# VF_Sine_CPU_Mainboard.net
KiCad netlist of a schematic drawn in EAGLE
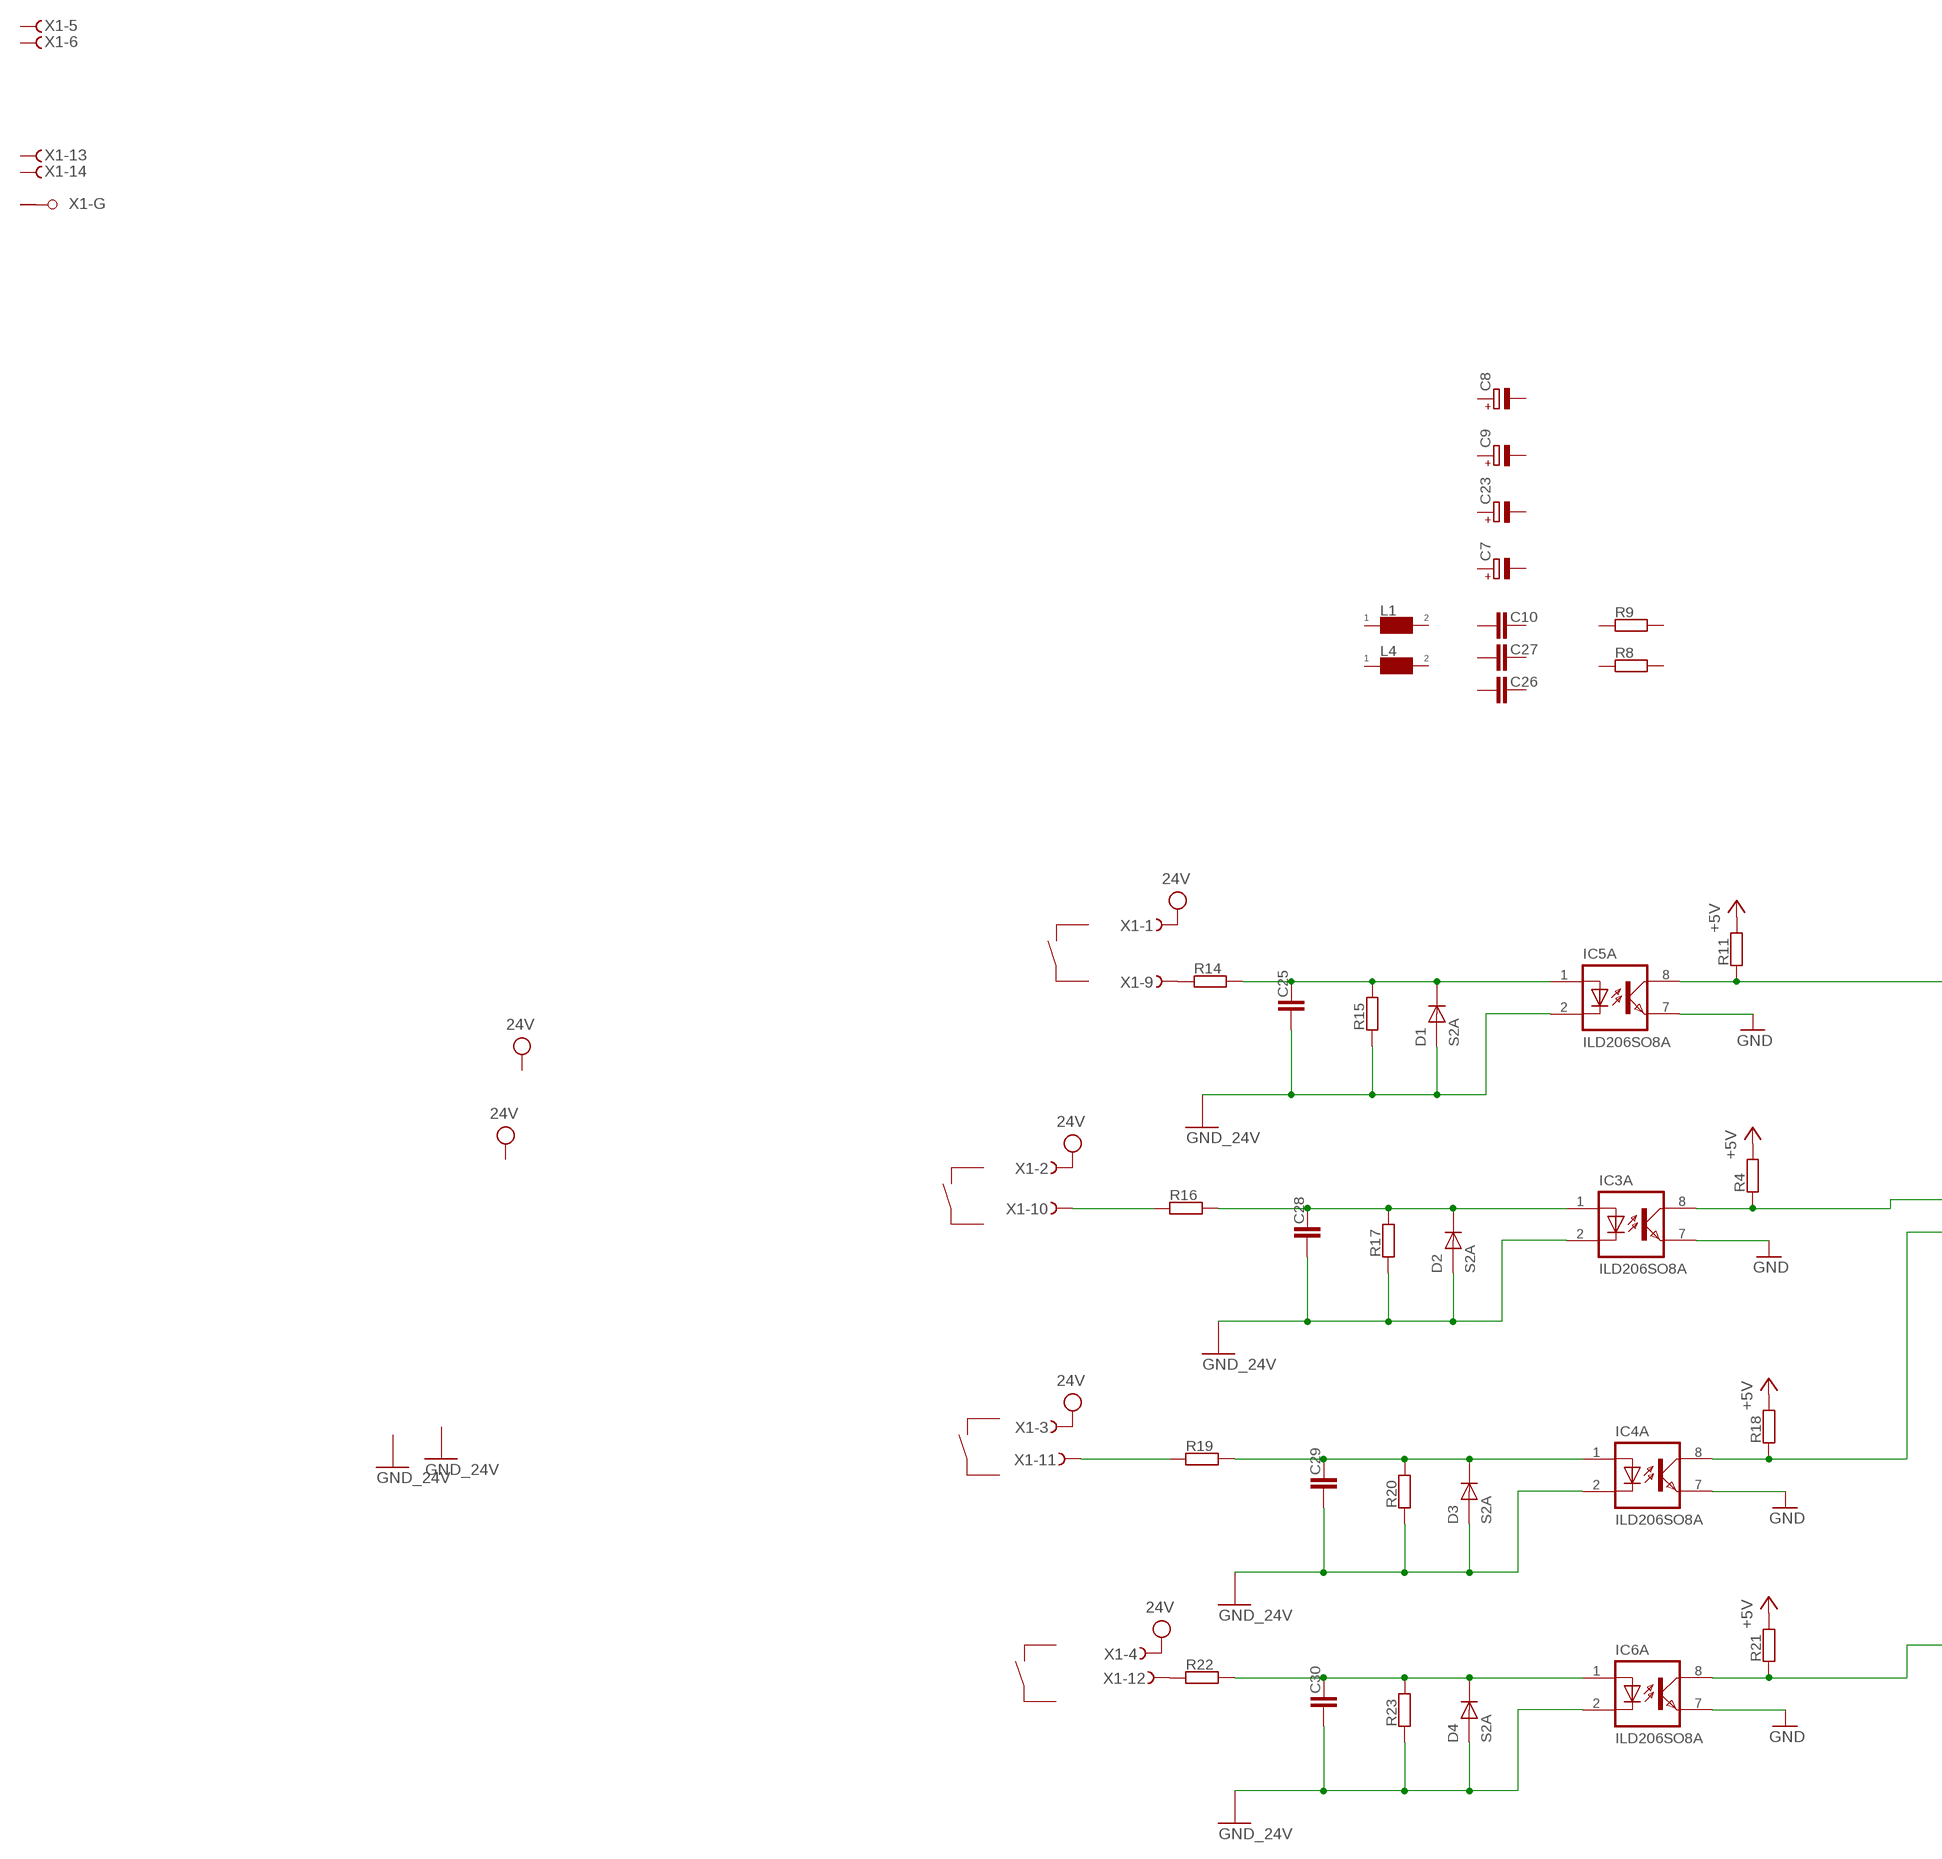
[diagram p0: schematic, sheet 1, part 1 of 3]
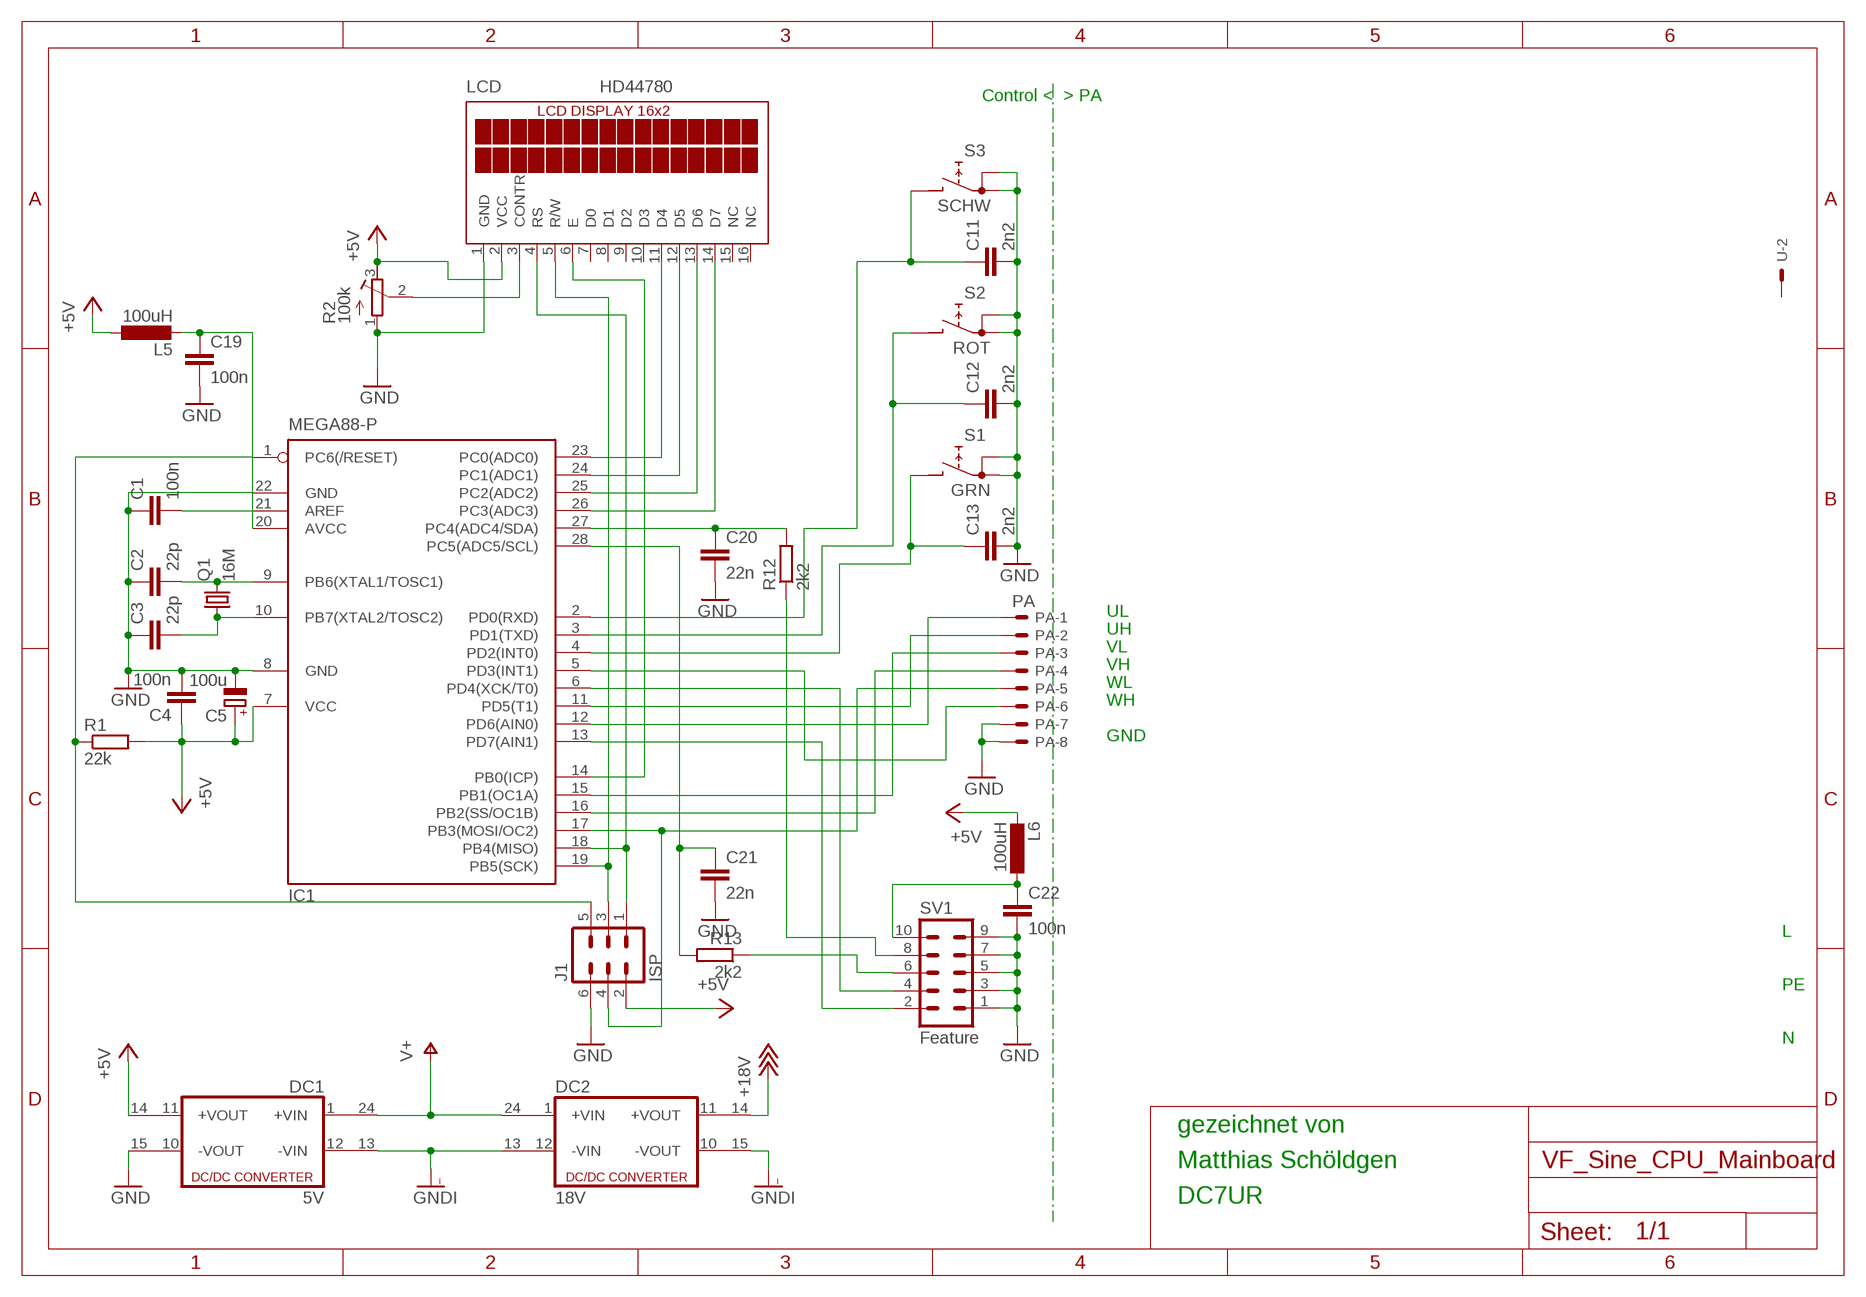
[diagram p1: schematic, sheet 1, part 2 of 3]
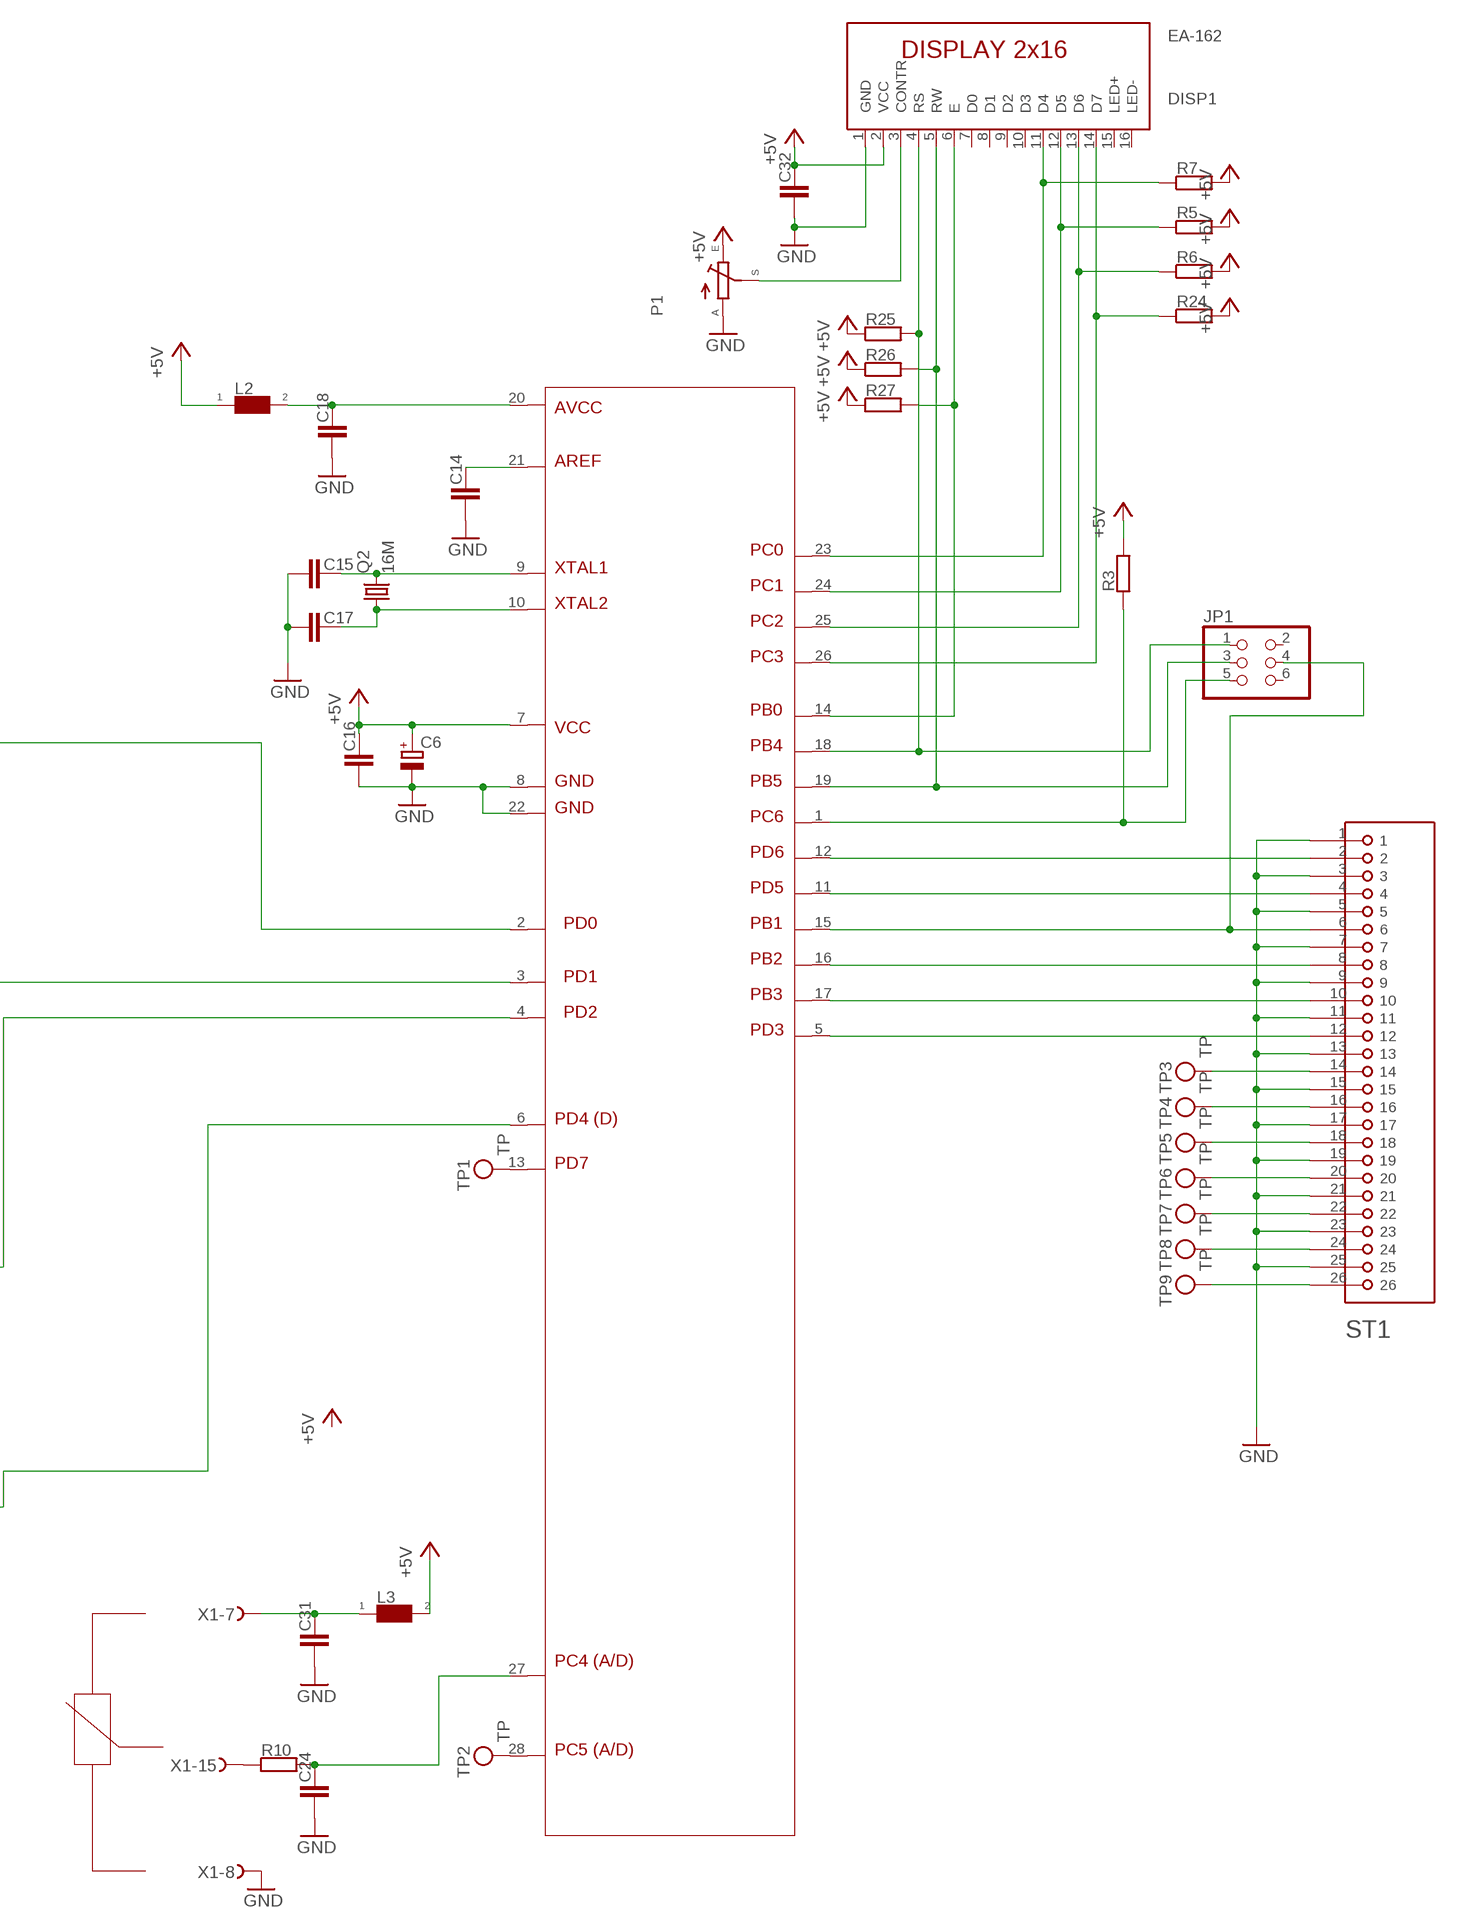
[diagram p2: schematic, sheet 1, part 3 of 3]

(export (version "E")
  (design (tool "Eeschema 10.0.6"))
  (components
    (comp (ref "C1")
      (value "100n")
      (footprint "eagle-import:C025-025X050")
      (libsource (lib "eagle-import") (part "C-EU025-025X050"))
    )
    (comp (ref "C2")
      (value "22p")
      (footprint "eagle-import:C025-025X050")
      (libsource (lib "eagle-import") (part "C-EU025-025X050"))
    )
    (comp (ref "C3")
      (value "22p")
      (footprint "eagle-import:C025-025X050")
      (libsource (lib "eagle-import") (part "C-EU025-025X050"))
    )
    (comp (ref "C4")
      (value "100n")
      (footprint "eagle-import:C025-025X050")
      (libsource (lib "eagle-import") (part "C-EU025-025X050"))
    )
    (comp (ref "C5")
      (value "100u")
      (footprint "eagle-import:B45181A")
      (libsource (lib "eagle-import") (part "CPOL-EUB45181A"))
    )
    (comp (ref "C6")
      (value "CPOL_EUPANASONIC_D")
      (footprint "eagle-import:PANASONIC_D")
      (libsource (lib "eagle-import") (part "CPOL_EUPANASONIC_D"))
    )
    (comp (ref "C7")
      (value "CPOL_EUPANASONIC_D")
      (footprint "eagle-import:PANASONIC_D")
      (libsource (lib "eagle-import") (part "CPOL_EUPANASONIC_D"))
    )
    (comp (ref "C8")
      (value "CPOL_EUPANASONIC_D")
      (footprint "eagle-import:PANASONIC_D")
      (libsource (lib "eagle-import") (part "CPOL_EUPANASONIC_D"))
    )
    (comp (ref "C9")
      (value "CPOL_EUPANASONIC_D")
      (footprint "eagle-import:PANASONIC_D")
      (libsource (lib "eagle-import") (part "CPOL_EUPANASONIC_D"))
    )
    (comp (ref "C10")
      (value "C-EUC0603")
      (footprint "eagle-import:C0603")
      (libsource (lib "eagle-import") (part "C-EUC0603"))
    )
    (comp (ref "C11")
      (value "2n2")
      (footprint "eagle-import:C025-025X050")
      (libsource (lib "eagle-import") (part "C-EU025-025X050"))
    )
    (comp (ref "C12")
      (value "2n2")
      (footprint "eagle-import:C025-025X050")
      (libsource (lib "eagle-import") (part "C-EU025-025X050"))
    )
    (comp (ref "C13")
      (value "2n2")
      (footprint "eagle-import:C025-025X050")
      (libsource (lib "eagle-import") (part "C-EU025-025X050"))
    )
    (comp (ref "C14")
      (value "C-EUC0603")
      (footprint "eagle-import:C0603")
      (libsource (lib "eagle-import") (part "C-EUC0603"))
    )
    (comp (ref "C15")
      (value "C-EUC0603")
      (footprint "eagle-import:C0603")
      (libsource (lib "eagle-import") (part "C-EUC0603"))
    )
    (comp (ref "C16")
      (value "C-EUC0603")
      (footprint "eagle-import:C0603")
      (libsource (lib "eagle-import") (part "C-EUC0603"))
    )
    (comp (ref "C17")
      (value "C-EUC0603")
      (footprint "eagle-import:C0603")
      (libsource (lib "eagle-import") (part "C-EUC0603"))
    )
    (comp (ref "C18")
      (value "C-EUC0603")
      (footprint "eagle-import:C0603")
      (libsource (lib "eagle-import") (part "C-EUC0603"))
    )
    (comp (ref "C19")
      (value "100n")
      (footprint "eagle-import:C050-030X075")
      (libsource (lib "eagle-import") (part "C-EU050-030X075"))
    )
    (comp (ref "C20")
      (value "22n")
      (footprint "eagle-import:C025-024X044")
      (libsource (lib "eagle-import") (part "C-EU025-024X044"))
    )
    (comp (ref "C21")
      (value "22n")
      (footprint "eagle-import:C025-024X044")
      (libsource (lib "eagle-import") (part "C-EU025-024X044"))
    )
    (comp (ref "C22")
      (value "100n")
      (footprint "eagle-import:C025-025X050")
      (libsource (lib "eagle-import") (part "C-EU025-025X050"))
    )
    (comp (ref "C23")
      (value "CPOL_EUPANASONIC_D")
      (footprint "eagle-import:PANASONIC_D")
      (libsource (lib "eagle-import") (part "CPOL_EUPANASONIC_D"))
    )
    (comp (ref "C24")
      (value "C-EUC0603")
      (footprint "eagle-import:C0603")
      (libsource (lib "eagle-import") (part "C-EUC0603"))
    )
    (comp (ref "C25")
      (value "C-EUC0603")
      (footprint "eagle-import:C0603")
      (libsource (lib "eagle-import") (part "C-EUC0603"))
    )
    (comp (ref "C26")
      (value "C-EUC0603")
      (footprint "eagle-import:C0603")
      (libsource (lib "eagle-import") (part "C-EUC0603"))
    )
    (comp (ref "C27")
      (value "C-EUC0603")
      (footprint "eagle-import:C0603")
      (libsource (lib "eagle-import") (part "C-EUC0603"))
    )
    (comp (ref "C28")
      (value "C-EUC0603")
      (footprint "eagle-import:C0603")
      (libsource (lib "eagle-import") (part "C-EUC0603"))
    )
    (comp (ref "C29")
      (value "C-EUC0603")
      (footprint "eagle-import:C0603")
      (libsource (lib "eagle-import") (part "C-EUC0603"))
    )
    (comp (ref "C30")
      (value "C-EUC0603")
      (footprint "eagle-import:C0603")
      (libsource (lib "eagle-import") (part "C-EUC0603"))
    )
    (comp (ref "C31")
      (value "C-EUC0603")
      (footprint "eagle-import:C0603")
      (libsource (lib "eagle-import") (part "C-EUC0603"))
    )
    (comp (ref "C32")
      (value "C-EUC0603")
      (footprint "eagle-import:C0603")
      (libsource (lib "eagle-import") (part "C-EUC0603"))
    )
    (comp (ref "D1")
      (value "S2A")
      (footprint "eagle-import:DO214AA")
      (libsource (lib "eagle-import") (part "S2A"))
    )
    (comp (ref "D2")
      (value "S2A")
      (footprint "eagle-import:DO214AA")
      (libsource (lib "eagle-import") (part "S2A"))
    )
    (comp (ref "D3")
      (value "S2A")
      (footprint "eagle-import:DO214AA")
      (libsource (lib "eagle-import") (part "S2A"))
    )
    (comp (ref "D4")
      (value "S2A")
      (footprint "eagle-import:DO214AA")
      (libsource (lib "eagle-import") (part "S2A"))
    )
    (comp (ref "DC1")
      (value "5V")
      (footprint "eagle-import:CMK")
      (libsource (lib "eagle-import") (part "DC213R"))
    )
    (comp (ref "DC2")
      (value "18V")
      (footprint "eagle-import:CMK")
      (libsource (lib "eagle-import") (part "DC213R"))
    )
    (comp (ref "DISP1")
      (value "EA-162")
      (footprint "eagle-import:EA-162")
      (libsource (lib "eagle-import") (part "EA-162"))
    )
    (comp (ref "IC1")
      (value "MEGA88-P")
      (footprint "eagle-import:DIL28-3")
      (libsource (lib "eagle-import") (part "MEGA8-P"))
    )
    (comp (ref "IC2")
      (value "ATMEGA328P_VAR")
      (footprint "eagle-import:DIL-28S")
      (libsource (lib "eagle-import") (part "ATMEGA328P_VAR"))
    )
    (comp (ref "IC3")
      (value "ILD206SO8A")
      (footprint "eagle-import:SO8A")
      (libsource (lib "eagle-import") (part "ILD206SO8A"))
    )
    (comp (ref "IC4")
      (value "ILD206SO8A")
      (footprint "eagle-import:SO8A")
      (libsource (lib "eagle-import") (part "ILD206SO8A"))
    )
    (comp (ref "IC5")
      (value "ILD206SO8A")
      (footprint "eagle-import:SO8A")
      (libsource (lib "eagle-import") (part "ILD206SO8A"))
    )
    (comp (ref "IC6")
      (value "ILD206SO8A")
      (footprint "eagle-import:SO8A")
      (libsource (lib "eagle-import") (part "ILD206SO8A"))
    )
    (comp (ref "J1")
      (value "ISP")
      (footprint "eagle-import:ML6")
      (libsource (lib "eagle-import") (part "ML6"))
    )
    (comp (ref "JP1")
      (value "PINHD-2X3")
      (footprint "eagle-import:2X03")
      (libsource (lib "eagle-import") (part "PINHD-2X3"))
    )
    (comp (ref "L1")
      (value "WE-PD2")
      (footprint "eagle-import:WE-PD2-M")
      (libsource (lib "eagle-import") (part "WE-PD2"))
    )
    (comp (ref "L2")
      (value "WE-PD2")
      (footprint "eagle-import:WE-PD2-M")
      (libsource (lib "eagle-import") (part "WE-PD2"))
    )
    (comp (ref "L3")
      (value "WE-PD2")
      (footprint "eagle-import:WE-PD2-M")
      (libsource (lib "eagle-import") (part "WE-PD2"))
    )
    (comp (ref "L4")
      (value "WE-PD2")
      (footprint "eagle-import:WE-PD2-M")
      (libsource (lib "eagle-import") (part "WE-PD2"))
    )
    (comp (ref "L5")
      (value "100uH")
      (footprint "eagle-import:0204_5")
      (libsource (lib "eagle-import") (part "L-EU0204/5"))
    )
    (comp (ref "L6")
      (value "100uH")
      (footprint "eagle-import:0204_5")
      (libsource (lib "eagle-import") (part "L-EU0204/5"))
    )
    (comp (ref "LCD")
      (value "HD44780")
      (footprint "eagle-import:TUXGR_16X2_R2")
      (libsource (lib "eagle-import") (part "TUXGR_16X2_R2"))
    )
    (comp (ref "P1")
      (value "TRIM_EU")
      (footprint "eagle-import:S64Y")
      (libsource (lib "eagle-import") (part "TRIM_EU"))
    )
    (comp (ref "PA")
      (value "PA")
      (footprint "eagle-import:22-23-2081")
      (libsource (lib "eagle-import") (part "22-23-2081"))
    )
    (comp (ref "Q1")
      (value "16M")
      (footprint "eagle-import:HC49_S")
      (libsource (lib "eagle-import") (part "CRYSTALHC49S"))
    )
    (comp (ref "Q2")
      (value "16M")
      (footprint "eagle-import:HC49_S")
      (libsource (lib "eagle-import") (part "CRYSTALHC49S"))
    )
    (comp (ref "R1")
      (value "22k")
      (footprint "eagle-import:0207_2V")
      (libsource (lib "eagle-import") (part "R-EU_0207/2V"))
    )
    (comp (ref "R2")
      (value "100k")
      (footprint "eagle-import:RTRIM4G_J")
      (libsource (lib "eagle-import") (part "R-TRIMM4G/J"))
    )
    (comp (ref "R3")
      (value "R-EUR0603")
      (footprint "eagle-import:R0603")
      (libsource (lib "eagle-import") (part "R-EUR0603"))
    )
    (comp (ref "R4")
      (value "R-EUR0603")
      (footprint "eagle-import:R0603")
      (libsource (lib "eagle-import") (part "R-EUR0603"))
    )
    (comp (ref "R5")
      (value "R-EUR0603")
      (footprint "eagle-import:R0603")
      (libsource (lib "eagle-import") (part "R-EUR0603"))
    )
    (comp (ref "R6")
      (value "R-EUR0603")
      (footprint "eagle-import:R0603")
      (libsource (lib "eagle-import") (part "R-EUR0603"))
    )
    (comp (ref "R7")
      (value "R-EUR0603")
      (footprint "eagle-import:R0603")
      (libsource (lib "eagle-import") (part "R-EUR0603"))
    )
    (comp (ref "R8")
      (value "R-EUR0603")
      (footprint "eagle-import:R0603")
      (libsource (lib "eagle-import") (part "R-EUR0603"))
    )
    (comp (ref "R9")
      (value "R-EUR0603")
      (footprint "eagle-import:R0603")
      (libsource (lib "eagle-import") (part "R-EUR0603"))
    )
    (comp (ref "R10")
      (value "R-EUR0603")
      (footprint "eagle-import:R0603")
      (libsource (lib "eagle-import") (part "R-EUR0603"))
    )
    (comp (ref "R11")
      (value "R-EUR0603")
      (footprint "eagle-import:R0603")
      (libsource (lib "eagle-import") (part "R-EUR0603"))
    )
    (comp (ref "R12")
      (value "2k2")
      (footprint "eagle-import:0204_5")
      (libsource (lib "eagle-import") (part "R-EU_0204/5"))
    )
    (comp (ref "R13")
      (value "2k2")
      (footprint "eagle-import:0204_5")
      (libsource (lib "eagle-import") (part "R-EU_0204/5"))
    )
    (comp (ref "R14")
      (value "R-EUR0603")
      (footprint "eagle-import:R0603")
      (libsource (lib "eagle-import") (part "R-EUR0603"))
    )
    (comp (ref "R15")
      (value "R-EUR0603")
      (footprint "eagle-import:R0603")
      (libsource (lib "eagle-import") (part "R-EUR0603"))
    )
    (comp (ref "R16")
      (value "R-EUR0603")
      (footprint "eagle-import:R0603")
      (libsource (lib "eagle-import") (part "R-EUR0603"))
    )
    (comp (ref "R17")
      (value "R-EUR0603")
      (footprint "eagle-import:R0603")
      (libsource (lib "eagle-import") (part "R-EUR0603"))
    )
    (comp (ref "R18")
      (value "R-EUR0603")
      (footprint "eagle-import:R0603")
      (libsource (lib "eagle-import") (part "R-EUR0603"))
    )
    (comp (ref "R19")
      (value "R-EUR0603")
      (footprint "eagle-import:R0603")
      (libsource (lib "eagle-import") (part "R-EUR0603"))
    )
    (comp (ref "R20")
      (value "R-EUR0603")
      (footprint "eagle-import:R0603")
      (libsource (lib "eagle-import") (part "R-EUR0603"))
    )
    (comp (ref "R21")
      (value "R-EUR0603")
      (footprint "eagle-import:R0603")
      (libsource (lib "eagle-import") (part "R-EUR0603"))
    )
    (comp (ref "R22")
      (value "R-EUR0603")
      (footprint "eagle-import:R0603")
      (libsource (lib "eagle-import") (part "R-EUR0603"))
    )
    (comp (ref "R23")
      (value "R-EUR0603")
      (footprint "eagle-import:R0603")
      (libsource (lib "eagle-import") (part "R-EUR0603"))
    )
    (comp (ref "R24")
      (value "R-EUR0603")
      (footprint "eagle-import:R0603")
      (libsource (lib "eagle-import") (part "R-EUR0603"))
    )
    (comp (ref "R25")
      (value "R-EUR0603")
      (footprint "eagle-import:R0603")
      (libsource (lib "eagle-import") (part "R-EUR0603"))
    )
    (comp (ref "R26")
      (value "R-EUR0603")
      (footprint "eagle-import:R0603")
      (libsource (lib "eagle-import") (part "R-EUR0603"))
    )
    (comp (ref "R27")
      (value "R-EUR0603")
      (footprint "eagle-import:R0603")
      (libsource (lib "eagle-import") (part "R-EUR0603"))
    )
    (comp (ref "S1")
      (value "GRN")
      (footprint "eagle-import:RDT1034")
      (libsource (lib "eagle-import") (part "RDT1034"))
    )
    (comp (ref "S2")
      (value "ROT")
      (footprint "eagle-import:RDT1034")
      (libsource (lib "eagle-import") (part "RDT1034"))
    )
    (comp (ref "S3")
      (value "SCHW")
      (footprint "eagle-import:RDT1034")
      (libsource (lib "eagle-import") (part "RDT1034"))
    )
    (comp (ref "ST1")
      (value "HD-26")
      (footprint "eagle-import:HD-26")
      (libsource (lib "eagle-import") (part "HD-26"))
    )
    (comp (ref "SV1")
      (value "Feature")
      (footprint "eagle-import:ML10")
      (libsource (lib "eagle-import") (part "ML10"))
    )
    (comp (ref "TP1") (value "TP") (footprint "eagle-import:TP") (libsource (lib "eagle-import") (part "TP")))
    (comp (ref "TP2") (value "TP") (footprint "eagle-import:TP") (libsource (lib "eagle-import") (part "TP")))
    (comp (ref "TP3") (value "TP") (footprint "eagle-import:TP") (libsource (lib "eagle-import") (part "TP")))
    (comp (ref "TP4") (value "TP") (footprint "eagle-import:TP") (libsource (lib "eagle-import") (part "TP")))
    (comp (ref "TP5") (value "TP") (footprint "eagle-import:TP") (libsource (lib "eagle-import") (part "TP")))
    (comp (ref "TP6") (value "TP") (footprint "eagle-import:TP") (libsource (lib "eagle-import") (part "TP")))
    (comp (ref "TP7") (value "TP") (footprint "eagle-import:TP") (libsource (lib "eagle-import") (part "TP")))
    (comp (ref "TP8") (value "TP") (footprint "eagle-import:TP") (libsource (lib "eagle-import") (part "TP")))
    (comp (ref "TP9") (value "TP") (footprint "eagle-import:TP") (libsource (lib "eagle-import") (part "TP")))
    (comp (ref "U")
      (value "5566-2")
      (footprint "eagle-import:5566-2")
      (libsource (lib "eagle-import") (part "5566-2"))
    )
    (comp (ref "X1")
      (value "F15VPS")
      (footprint "eagle-import:F15VP")
      (libsource (lib "eagle-import") (part "F15VPS"))
    )
  )
  (nets
    (net (code "1") (name "+5V") (class "Default")
      (node (ref "C16") (pin "2") (pinfunction "2_2") (pintype "passive"))
      (node (ref "C32") (pin "2") (pinfunction "2_2") (pintype "passive"))
      (node (ref "C4") (pin "1") (pinfunction "1_1") (pintype "passive"))
      (node (ref "C5") (pin "+") (pinfunction "+_+") (pintype "passive"))
      (node (ref "C6") (pin "+") (pinfunction "+_+") (pintype "passive"))
      (node (ref "DC1") (pin "14") (pinfunction "+VOUT1_14") (pintype "passive"))
      (node (ref "DISP1") (pin "2") (pinfunction "VCC_2") (pintype "power_in"))
      (node (ref "IC1") (pin "7") (pinfunction "VCC_7") (pintype "power_in"))
      (node (ref "IC2") (pin "7") (pinfunction "SK1_7") (pintype "passive"))
      (node (ref "J1") (pin "2") (pinfunction "2_2") (pintype "passive"))
      (node (ref "L2") (pin "1") (pinfunction "1_1") (pintype "passive"))
      (node (ref "L3") (pin "2") (pinfunction "2_2") (pintype "passive"))
      (node (ref "L5") (pin "1") (pinfunction "1_1") (pintype "passive"))
      (node (ref "L6") (pin "2") (pinfunction "2_2") (pintype "passive"))
      (node (ref "LCD") (pin "2") (pinfunction "VCC_2") (pintype "power_in"))
      (node (ref "P1") (pin "E") (pinfunction "E_E") (pintype "passive"))
      (node (ref "R1") (pin "2") (pinfunction "2_2") (pintype "passive"))
      (node (ref "R11") (pin "2") (pinfunction "2_2") (pintype "passive"))
      (node (ref "R18") (pin "2") (pinfunction "2_2") (pintype "passive"))
      (node (ref "R2") (pin "3") (pinfunction "A_3") (pintype "passive"))
      (node (ref "R21") (pin "2") (pinfunction "2_2") (pintype "passive"))
      (node (ref "R24") (pin "2") (pinfunction "2_2") (pintype "passive"))
      (node (ref "R25") (pin "1") (pinfunction "1_1") (pintype "passive"))
      (node (ref "R26") (pin "1") (pinfunction "1_1") (pintype "passive"))
      (node (ref "R27") (pin "1") (pinfunction "1_1") (pintype "passive"))
      (node (ref "R3") (pin "2") (pinfunction "2_2") (pintype "passive"))
      (node (ref "R4") (pin "2") (pinfunction "2_2") (pintype "passive"))
      (node (ref "R5") (pin "2") (pinfunction "2_2") (pintype "passive"))
      (node (ref "R6") (pin "2") (pinfunction "2_2") (pintype "passive"))
      (node (ref "R7") (pin "2") (pinfunction "2_2") (pintype "passive"))
    )
    (net (code "2") (name "+18V") (class "Default")
      (node (ref "DC2") (pin "14") (pinfunction "+VOUT1_14") (pintype "passive"))
    )
    (net (code "3") (name "24V") (class "Default")
      (node (ref "X1") (pin "1") (pinfunction "F_1") (pintype "passive"))
      (node (ref "X1") (pin "2") (pinfunction "F_2") (pintype "passive"))
      (node (ref "X1") (pin "3") (pinfunction "F_3") (pintype "passive"))
      (node (ref "X1") (pin "4") (pinfunction "F_4") (pintype "passive"))
    )
    (net (code "4") (name "GND") (class "Default")
      (node (ref "C1") (pin "1") (pinfunction "1_1") (pintype "passive"))
      (node (ref "C11") (pin "2") (pinfunction "2_2") (pintype "passive"))
      (node (ref "C12") (pin "2") (pinfunction "2_2") (pintype "passive"))
      (node (ref "C13") (pin "2") (pinfunction "2_2") (pintype "passive"))
      (node (ref "C14") (pin "1") (pinfunction "1_1") (pintype "passive"))
      (node (ref "C15") (pin "1") (pinfunction "1_1") (pintype "passive"))
      (node (ref "C16") (pin "1") (pinfunction "1_1") (pintype "passive"))
      (node (ref "C17") (pin "1") (pinfunction "1_1") (pintype "passive"))
      (node (ref "C18") (pin "1") (pinfunction "1_1") (pintype "passive"))
      (node (ref "C19") (pin "2") (pinfunction "2_2") (pintype "passive"))
      (node (ref "C2") (pin "1") (pinfunction "1_1") (pintype "passive"))
      (node (ref "C20") (pin "2") (pinfunction "2_2") (pintype "passive"))
      (node (ref "C21") (pin "2") (pinfunction "2_2") (pintype "passive"))
      (node (ref "C22") (pin "2") (pinfunction "2_2") (pintype "passive"))
      (node (ref "C24") (pin "1") (pinfunction "1_1") (pintype "passive"))
      (node (ref "C3") (pin "1") (pinfunction "1_1") (pintype "passive"))
      (node (ref "C31") (pin "1") (pinfunction "1_1") (pintype "passive"))
      (node (ref "C32") (pin "1") (pinfunction "1_1") (pintype "passive"))
      (node (ref "C4") (pin "2") (pinfunction "2_2") (pintype "passive"))
      (node (ref "C5") (pin "-") (pinfunction "-_-") (pintype "passive"))
      (node (ref "C6") (pin "-") (pinfunction "-_-") (pintype "passive"))
      (node (ref "DC1") (pin "15") (pinfunction "-VOUT1_15") (pintype "passive"))
      (node (ref "DISP1") (pin "1") (pinfunction "GND_1") (pintype "power_in"))
      (node (ref "IC1") (pin "22") (pinfunction "GND_22") (pintype "power_in"))
      (node (ref "IC1") (pin "8") (pinfunction "GND_8") (pintype "power_in"))
      (node (ref "IC2") (pin "22") (pinfunction "SK1_22") (pintype "passive"))
      (node (ref "IC2") (pin "8") (pinfunction "SK1_8") (pintype "passive"))
      (node (ref "IC3") (pin "7") (pinfunction "EMIT_7") (pintype "passive"))
      (node (ref "IC4") (pin "7") (pinfunction "EMIT_7") (pintype "passive"))
      (node (ref "IC5") (pin "7") (pinfunction "EMIT_7") (pintype "passive"))
      (node (ref "IC6") (pin "7") (pinfunction "EMIT_7") (pintype "passive"))
      (node (ref "J1") (pin "6") (pinfunction "6_6") (pintype "passive"))
      (node (ref "LCD") (pin "1") (pinfunction "GND_1") (pintype "power_in"))
      (node (ref "P1") (pin "A") (pinfunction "A_A") (pintype "passive"))
      (node (ref "PA") (pin "7") (pinfunction "S_7") (pintype "passive"))
      (node (ref "PA") (pin "8") (pinfunction "S_8") (pintype "passive"))
      (node (ref "R2") (pin "1") (pinfunction "E_1") (pintype "passive"))
      (node (ref "S1") (pin "A") (pinfunction "A_A") (pintype "passive"))
      (node (ref "S1") (pin "A1") (pinfunction "A1_A1") (pintype "passive"))
      (node (ref "S2") (pin "A") (pinfunction "A_A") (pintype "passive"))
      (node (ref "S2") (pin "A1") (pinfunction "A1_A1") (pintype "passive"))
      (node (ref "S3") (pin "A") (pinfunction "A_A") (pintype "passive"))
      (node (ref "S3") (pin "A1") (pinfunction "A1_A1") (pintype "passive"))
      (node (ref "ST1") (pin "1") (pinfunction "1_1") (pintype "bidirectional"))
      (node (ref "ST1") (pin "11") (pinfunction "11_11") (pintype "bidirectional"))
      (node (ref "ST1") (pin "13") (pinfunction "13_13") (pintype "bidirectional"))
      (node (ref "ST1") (pin "15") (pinfunction "15_15") (pintype "bidirectional"))
      (node (ref "ST1") (pin "17") (pinfunction "17_17") (pintype "bidirectional"))
      (node (ref "ST1") (pin "19") (pinfunction "19_19") (pintype "bidirectional"))
      (node (ref "ST1") (pin "21") (pinfunction "21_21") (pintype "bidirectional"))
      (node (ref "ST1") (pin "23") (pinfunction "23_23") (pintype "bidirectional"))
      (node (ref "ST1") (pin "25") (pinfunction "25_25") (pintype "bidirectional"))
      (node (ref "ST1") (pin "3") (pinfunction "3_3") (pintype "bidirectional"))
      (node (ref "ST1") (pin "5") (pinfunction "5_5") (pintype "bidirectional"))
      (node (ref "ST1") (pin "7") (pinfunction "7_7") (pintype "bidirectional"))
      (node (ref "ST1") (pin "9") (pinfunction "9_9") (pintype "bidirectional"))
      (node (ref "SV1") (pin "1") (pinfunction "1_1") (pintype "passive"))
      (node (ref "SV1") (pin "3") (pinfunction "3_3") (pintype "passive"))
      (node (ref "SV1") (pin "5") (pinfunction "5_5") (pintype "passive"))
      (node (ref "SV1") (pin "7") (pinfunction "7_7") (pintype "passive"))
      (node (ref "SV1") (pin "9") (pinfunction "9_9") (pintype "passive"))
      (node (ref "X1") (pin "8") (pinfunction "F_8") (pintype "passive"))
    )
    (net (code "5") (name "GNDI") (class "Default")
      (node (ref "DC1") (pin "13") (pinfunction "-VIN1_13") (pintype "passive"))
      (node (ref "DC2") (pin "13") (pinfunction "-VIN1_13") (pintype "passive"))
      (node (ref "DC2") (pin "15") (pinfunction "-VOUT1_15") (pintype "passive"))
    )
    (net (code "6") (name "GND_24V") (class "Default")
      (node (ref "C25") (pin "1") (pinfunction "1_1") (pintype "passive"))
      (node (ref "C28") (pin "1") (pinfunction "1_1") (pintype "passive"))
      (node (ref "C29") (pin "1") (pinfunction "1_1") (pintype "passive"))
      (node (ref "C30") (pin "1") (pinfunction "1_1") (pintype "passive"))
      (node (ref "D1") (pin "A") (pinfunction "A_A") (pintype "passive"))
      (node (ref "D2") (pin "A") (pinfunction "A_A") (pintype "passive"))
      (node (ref "D3") (pin "A") (pinfunction "A_A") (pintype "passive"))
      (node (ref "D4") (pin "A") (pinfunction "A_A") (pintype "passive"))
      (node (ref "IC3") (pin "2") (pinfunction "C_2") (pintype "passive"))
      (node (ref "IC4") (pin "2") (pinfunction "C_2") (pintype "passive"))
      (node (ref "IC5") (pin "2") (pinfunction "C_2") (pintype "passive"))
      (node (ref "IC6") (pin "2") (pinfunction "C_2") (pintype "passive"))
      (node (ref "R15") (pin "1") (pinfunction "1_1") (pintype "passive"))
      (node (ref "R17") (pin "1") (pinfunction "1_1") (pintype "passive"))
      (node (ref "R20") (pin "1") (pinfunction "1_1") (pintype "passive"))
      (node (ref "R23") (pin "1") (pinfunction "1_1") (pintype "passive"))
    )
    (net (code "7") (name "Net-(C22-Pad1)") (class "Default")
      (node (ref "C22") (pin "1") (pinfunction "1_1") (pintype "passive"))
      (node (ref "L6") (pin "1") (pinfunction "1_1") (pintype "passive"))
      (node (ref "SV1") (pin "10") (pinfunction "10_10") (pintype "passive"))
    )
    (net (code "8") (name "Net-(D1-C)") (class "Default")
      (node (ref "C25") (pin "2") (pinfunction "2_2") (pintype "passive"))
      (node (ref "D1") (pin "K") (pinfunction "C_K") (pintype "passive"))
      (node (ref "IC5") (pin "1") (pinfunction "A_1") (pintype "passive"))
      (node (ref "R14") (pin "2") (pinfunction "2_2") (pintype "passive"))
      (node (ref "R15") (pin "2") (pinfunction "2_2") (pintype "passive"))
    )
    (net (code "9") (name "Net-(D2-C)") (class "Default")
      (node (ref "C28") (pin "2") (pinfunction "2_2") (pintype "passive"))
      (node (ref "D2") (pin "K") (pinfunction "C_K") (pintype "passive"))
      (node (ref "IC3") (pin "1") (pinfunction "A_1") (pintype "passive"))
      (node (ref "R16") (pin "2") (pinfunction "2_2") (pintype "passive"))
      (node (ref "R17") (pin "2") (pinfunction "2_2") (pintype "passive"))
    )
    (net (code "10") (name "Net-(D3-C)") (class "Default")
      (node (ref "C29") (pin "2") (pinfunction "2_2") (pintype "passive"))
      (node (ref "D3") (pin "K") (pinfunction "C_K") (pintype "passive"))
      (node (ref "IC4") (pin "1") (pinfunction "A_1") (pintype "passive"))
      (node (ref "R19") (pin "2") (pinfunction "2_2") (pintype "passive"))
      (node (ref "R20") (pin "2") (pinfunction "2_2") (pintype "passive"))
    )
    (net (code "11") (name "Net-(D4-C)") (class "Default")
      (node (ref "C30") (pin "2") (pinfunction "2_2") (pintype "passive"))
      (node (ref "D4") (pin "K") (pinfunction "C_K") (pintype "passive"))
      (node (ref "IC6") (pin "1") (pinfunction "A_1") (pintype "passive"))
      (node (ref "R22") (pin "2") (pinfunction "2_2") (pintype "passive"))
      (node (ref "R23") (pin "2") (pinfunction "2_2") (pintype "passive"))
    )
    (net (code "12") (name "Net-(DISP1-CONTR)") (class "Default")
      (node (ref "DISP1") (pin "3") (pinfunction "CONTR_3") (pintype "bidirectional"))
      (node (ref "P1") (pin "S") (pinfunction "S_S") (pintype "passive"))
    )
    (net (code "13") (name "Net-(DISP1-D4)") (class "Default")
      (node (ref "DISP1") (pin "11") (pinfunction "D4_11") (pintype "bidirectional"))
      (node (ref "IC2") (pin "23") (pinfunction "SK1_23") (pintype "passive"))
      (node (ref "R7") (pin "1") (pinfunction "1_1") (pintype "passive"))
    )
    (net (code "14") (name "Net-(DISP1-D5)") (class "Default")
      (node (ref "DISP1") (pin "12") (pinfunction "D5_12") (pintype "bidirectional"))
      (node (ref "IC2") (pin "24") (pinfunction "SK1_24") (pintype "passive"))
      (node (ref "R5") (pin "1") (pinfunction "1_1") (pintype "passive"))
    )
    (net (code "15") (name "Net-(DISP1-D6)") (class "Default")
      (node (ref "DISP1") (pin "13") (pinfunction "D6_13") (pintype "bidirectional"))
      (node (ref "IC2") (pin "25") (pinfunction "SK1_25") (pintype "passive"))
      (node (ref "R6") (pin "1") (pinfunction "1_1") (pintype "passive"))
    )
    (net (code "16") (name "Net-(DISP1-D7)") (class "Default")
      (node (ref "DISP1") (pin "14") (pinfunction "D7_14") (pintype "bidirectional"))
      (node (ref "IC2") (pin "26") (pinfunction "SK1_26") (pintype "passive"))
      (node (ref "R24") (pin "1") (pinfunction "1_1") (pintype "passive"))
    )
    (net (code "17") (name "Net-(DISP1-E)") (class "Default")
      (node (ref "DISP1") (pin "6") (pinfunction "E_6") (pintype "bidirectional"))
      (node (ref "IC2") (pin "14") (pinfunction "SK1_14") (pintype "passive"))
      (node (ref "R27") (pin "2") (pinfunction "2_2") (pintype "passive"))
    )
    (net (code "18") (name "Net-(DISP1-RS)") (class "Default")
      (node (ref "DISP1") (pin "4") (pinfunction "RS_4") (pintype "bidirectional"))
      (node (ref "IC2") (pin "18") (pinfunction "SK1_18") (pintype "passive"))
      (node (ref "JP1") (pin "1") (pinfunction "1_1") (pintype "passive"))
      (node (ref "R25") (pin "2") (pinfunction "2_2") (pintype "passive"))
    )
    (net (code "19") (name "Net-(DISP1-RW)") (class "Default")
      (node (ref "DISP1") (pin "5") (pinfunction "RW_5") (pintype "bidirectional"))
      (node (ref "IC2") (pin "19") (pinfunction "SK1_19") (pintype "passive"))
      (node (ref "JP1") (pin "3") (pinfunction "3_3") (pintype "passive"))
      (node (ref "R26") (pin "2") (pinfunction "2_2") (pintype "passive"))
    )
    (net (code "20") (name "Net-(IC1-AREF)") (class "Default")
      (node (ref "C1") (pin "2") (pinfunction "2_2") (pintype "passive"))
      (node (ref "IC1") (pin "21") (pinfunction "AREF_21") (pintype "passive"))
    )
    (net (code "21") (name "Net-(IC1-AVCC)") (class "Default")
      (node (ref "C19") (pin "1") (pinfunction "1_1") (pintype "passive"))
      (node (ref "IC1") (pin "20") (pinfunction "AVCC_20") (pintype "power_in"))
      (node (ref "L5") (pin "2") (pinfunction "2_2") (pintype "passive"))
    )
    (net (code "22") (name "Net-(IC1-PB0(ICP))") (class "Default")
      (node (ref "IC1") (pin "14") (pinfunction "PB0(ICP)_14") (pintype "bidirectional"))
      (node (ref "LCD") (pin "6") (pinfunction "E_6") (pintype "input"))
    )
    (net (code "23") (name "Net-(IC1-PB1(OC1A))") (class "Default")
      (node (ref "IC1") (pin "15") (pinfunction "PB1(OC1A)_15") (pintype "bidirectional"))
      (node (ref "PA") (pin "3") (pinfunction "S_3") (pintype "passive"))
    )
    (net (code "24") (name "Net-(IC1-PB2(SS{slash}OC1B))") (class "Default")
      (node (ref "IC1") (pin "16") (pinfunction "PB2(SS/OC1B)_16") (pintype "bidirectional"))
      (node (ref "PA") (pin "4") (pinfunction "S_4") (pintype "passive"))
    )
    (net (code "25") (name "Net-(IC1-PB3(MOSI{slash}OC2))") (class "Default")
      (node (ref "IC1") (pin "17") (pinfunction "PB3(MOSI/OC2)_17") (pintype "bidirectional"))
      (node (ref "J1") (pin "4") (pinfunction "4_4") (pintype "passive"))
      (node (ref "PA") (pin "5") (pinfunction "S_5") (pintype "passive"))
    )
    (net (code "26") (name "Net-(IC1-PB4(MISO))") (class "Default")
      (node (ref "IC1") (pin "18") (pinfunction "PB4(MISO)_18") (pintype "bidirectional"))
      (node (ref "J1") (pin "1") (pinfunction "1_1") (pintype "passive"))
      (node (ref "LCD") (pin "4") (pinfunction "RS_4") (pintype "input"))
    )
    (net (code "27") (name "Net-(IC1-PB5(SCK))") (class "Default")
      (node (ref "IC1") (pin "19") (pinfunction "PB5(SCK)_19") (pintype "bidirectional"))
      (node (ref "J1") (pin "3") (pinfunction "3_3") (pintype "passive"))
      (node (ref "LCD") (pin "5") (pinfunction "R/W_5") (pintype "input"))
    )
    (net (code "28") (name "Net-(IC1-PB6(XTAL1{slash}TOSC1))") (class "Default")
      (node (ref "C2") (pin "2") (pinfunction "2_2") (pintype "passive"))
      (node (ref "IC1") (pin "9") (pinfunction "PB6(XTAL1/TOSC1)_9") (pintype "bidirectional"))
      (node (ref "Q1") (pin "2") (pinfunction "2_2") (pintype "passive"))
    )
    (net (code "29") (name "Net-(IC1-PB7(XTAL2{slash}TOSC2))") (class "Default")
      (node (ref "C3") (pin "2") (pinfunction "2_2") (pintype "passive"))
      (node (ref "IC1") (pin "10") (pinfunction "PB7(XTAL2/TOSC2)_10") (pintype "bidirectional"))
      (node (ref "Q1") (pin "1") (pinfunction "1_1") (pintype "passive"))
    )
    (net (code "30") (name "Net-(IC1-PC0(ADC0))") (class "Default")
      (node (ref "IC1") (pin "23") (pinfunction "PC0(ADC0)_23") (pintype "bidirectional"))
      (node (ref "LCD") (pin "11") (pinfunction "D4_11") (pintype "input"))
    )
    (net (code "31") (name "Net-(IC1-PC1(ADC1))") (class "Default")
      (node (ref "IC1") (pin "24") (pinfunction "PC1(ADC1)_24") (pintype "bidirectional"))
      (node (ref "LCD") (pin "12") (pinfunction "D5_12") (pintype "input"))
    )
    (net (code "32") (name "Net-(IC1-PC2(ADC2))") (class "Default")
      (node (ref "IC1") (pin "25") (pinfunction "PC2(ADC2)_25") (pintype "bidirectional"))
      (node (ref "LCD") (pin "13") (pinfunction "D6_13") (pintype "input"))
    )
    (net (code "33") (name "Net-(IC1-PC3(ADC3))") (class "Default")
      (node (ref "IC1") (pin "26") (pinfunction "PC3(ADC3)_26") (pintype "bidirectional"))
      (node (ref "LCD") (pin "14") (pinfunction "D7_14") (pintype "input"))
    )
    (net (code "34") (name "Net-(IC1-PC4(ADC4{slash}SDA))") (class "Default")
      (node (ref "C20") (pin "1") (pinfunction "1_1") (pintype "passive"))
      (node (ref "IC1") (pin "27") (pinfunction "PC4(ADC4/SDA)_27") (pintype "bidirectional"))
      (node (ref "R12") (pin "2") (pinfunction "2_2") (pintype "passive"))
    )
    (net (code "35") (name "Net-(IC1-PC5(ADC5{slash}SCL))") (class "Default")
      (node (ref "C21") (pin "1") (pinfunction "1_1") (pintype "passive"))
      (node (ref "IC1") (pin "28") (pinfunction "PC5(ADC5/SCL)_28") (pintype "bidirectional"))
      (node (ref "R13") (pin "2") (pinfunction "2_2") (pintype "passive"))
    )
    (net (code "36") (name "Net-(IC1-PC6({slash}RESET))") (class "Default")
      (node (ref "IC1") (pin "1") (pinfunction "PC6(/RESET)_1") (pintype "bidirectional"))
      (node (ref "J1") (pin "5") (pinfunction "5_5") (pintype "passive"))
      (node (ref "R1") (pin "1") (pinfunction "1_1") (pintype "passive"))
    )
    (net (code "37") (name "Net-(IC1-PD0(RXD))") (class "Default")
      (node (ref "C11") (pin "1") (pinfunction "1_1") (pintype "passive"))
      (node (ref "IC1") (pin "2") (pinfunction "PD0(RXD)_2") (pintype "bidirectional"))
      (node (ref "S3") (pin "B") (pinfunction "B_B") (pintype "passive"))
    )
    (net (code "38") (name "Net-(IC1-PD1(TXD))") (class "Default")
      (node (ref "C12") (pin "1") (pinfunction "1_1") (pintype "passive"))
      (node (ref "IC1") (pin "3") (pinfunction "PD1(TXD)_3") (pintype "bidirectional"))
      (node (ref "S2") (pin "B") (pinfunction "B_B") (pintype "passive"))
    )
    (net (code "39") (name "Net-(IC1-PD2(INT0))") (class "Default")
      (node (ref "C13") (pin "1") (pinfunction "1_1") (pintype "passive"))
      (node (ref "IC1") (pin "4") (pinfunction "PD2(INT0)_4") (pintype "bidirectional"))
      (node (ref "S1") (pin "B") (pinfunction "B_B") (pintype "passive"))
    )
    (net (code "40") (name "Net-(IC1-PD3(INT1))") (class "Default")
      (node (ref "IC1") (pin "5") (pinfunction "PD3(INT1)_5") (pintype "bidirectional"))
      (node (ref "PA") (pin "6") (pinfunction "S_6") (pintype "passive"))
    )
    (net (code "41") (name "Net-(IC1-PD4(XCK{slash}T0))") (class "Default")
      (node (ref "IC1") (pin "6") (pinfunction "PD4(XCK/T0)_6") (pintype "bidirectional"))
      (node (ref "SV1") (pin "4") (pinfunction "4_4") (pintype "passive"))
    )
    (net (code "42") (name "Net-(IC1-PD5(T1))") (class "Default")
      (node (ref "IC1") (pin "11") (pinfunction "PD5(T1)_11") (pintype "bidirectional"))
      (node (ref "PA") (pin "2") (pinfunction "S_2") (pintype "passive"))
    )
    (net (code "43") (name "Net-(IC1-PD6(AIN0))") (class "Default")
      (node (ref "IC1") (pin "12") (pinfunction "PD6(AIN0)_12") (pintype "bidirectional"))
      (node (ref "PA") (pin "1") (pinfunction "S_1") (pintype "passive"))
    )
    (net (code "44") (name "Net-(IC1-PD7(AIN1))") (class "Default")
      (node (ref "IC1") (pin "13") (pinfunction "PD7(AIN1)_13") (pintype "bidirectional"))
      (node (ref "SV1") (pin "2") (pinfunction "2_2") (pintype "passive"))
    )
    (net (code "45") (name "Net-(IC2A-SK1)") (class "Default")
      (node (ref "IC2") (pin "1") (pinfunction "SK1_1") (pintype "passive"))
      (node (ref "JP1") (pin "5") (pinfunction "5_5") (pintype "passive"))
      (node (ref "R3") (pin "1") (pinfunction "1_1") (pintype "passive"))
    )
    (net (code "46") (name "Net-(IC2AB-SK1)") (class "Default")
      (node (ref "C15") (pin "2") (pinfunction "2_2") (pintype "passive"))
      (node (ref "IC2") (pin "9") (pinfunction "SK1_9") (pintype "passive"))
      (node (ref "Q2") (pin "2") (pinfunction "2_2") (pintype "passive"))
    )
    (net (code "47") (name "Net-(IC2B-SK1)") (class "Default")
      (node (ref "C17") (pin "2") (pinfunction "2_2") (pintype "passive"))
      (node (ref "IC2") (pin "10") (pinfunction "SK1_10") (pintype "passive"))
      (node (ref "Q2") (pin "1") (pinfunction "1_1") (pintype "passive"))
    )
    (net (code "48") (name "Net-(IC2C-SK1)") (class "Default")
      (node (ref "IC2") (pin "11") (pinfunction "SK1_11") (pintype "passive"))
      (node (ref "ST1") (pin "4") (pinfunction "4_4") (pintype "bidirectional"))
    )
    (net (code "49") (name "Net-(IC2D-SK1)") (class "Default")
      (node (ref "IC2") (pin "12") (pinfunction "SK1_12") (pintype "passive"))
      (node (ref "ST1") (pin "2") (pinfunction "2_2") (pintype "bidirectional"))
    )
    (net (code "50") (name "Net-(IC2E-SK1)") (class "Default")
      (node (ref "IC2") (pin "13") (pinfunction "SK1_13") (pintype "passive"))
      (node (ref "TP1") (pin "TP") (pinfunction "TP_13_TP") (pintype "bidirectional"))
    )
    (net (code "51") (name "Net-(IC2G-SK1)") (class "Default")
      (node (ref "IC2") (pin "15") (pinfunction "SK1_15") (pintype "passive"))
      (node (ref "JP1") (pin "4") (pinfunction "4_4") (pintype "passive"))
      (node (ref "ST1") (pin "6") (pinfunction "6_6") (pintype "bidirectional"))
    )
    (net (code "52") (name "Net-(IC2H-SK1)") (class "Default")
      (node (ref "IC2") (pin "16") (pinfunction "SK1_16") (pintype "passive"))
      (node (ref "ST1") (pin "8") (pinfunction "8_8") (pintype "bidirectional"))
    )
    (net (code "53") (name "Net-(IC2I-SK1)") (class "Default")
      (node (ref "IC2") (pin "17") (pinfunction "SK1_17") (pintype "passive"))
      (node (ref "ST1") (pin "10") (pinfunction "10_10") (pintype "bidirectional"))
    )
    (net (code "54") (name "Net-(IC2L-SK1)") (class "Default")
      (node (ref "IC2") (pin "2") (pinfunction "SK1_2") (pintype "passive"))
      (node (ref "IC5") (pin "8") (pinfunction "COL_8") (pintype "passive"))
      (node (ref "R11") (pin "1") (pinfunction "1_1") (pintype "passive"))
    )
    (net (code "55") (name "Net-(IC2M-SK1)") (class "Default")
      (node (ref "C18") (pin "2") (pinfunction "2_2") (pintype "passive"))
      (node (ref "IC2") (pin "20") (pinfunction "SK1_20") (pintype "passive"))
      (node (ref "L2") (pin "2") (pinfunction "2_2") (pintype "passive"))
    )
    (net (code "56") (name "Net-(IC2N-SK1)") (class "Default")
      (node (ref "C14") (pin "2") (pinfunction "2_2") (pintype "passive"))
      (node (ref "IC2") (pin "21") (pinfunction "SK1_21") (pintype "passive"))
    )
    (net (code "57") (name "Net-(IC2T-SK1)") (class "Default")
      (node (ref "C24") (pin "2") (pinfunction "2_2") (pintype "passive"))
      (node (ref "IC2") (pin "27") (pinfunction "SK1_27") (pintype "passive"))
      (node (ref "R10") (pin "2") (pinfunction "2_2") (pintype "passive"))
    )
    (net (code "58") (name "Net-(IC2U-SK1)") (class "Default")
      (node (ref "IC2") (pin "28") (pinfunction "SK1_28") (pintype "passive"))
      (node (ref "TP2") (pin "TP") (pinfunction "TP_13_TP") (pintype "bidirectional"))
    )
    (net (code "59") (name "Net-(IC2V-SK1)") (class "Default")
      (node (ref "IC2") (pin "3") (pinfunction "SK1_3") (pintype "passive"))
      (node (ref "IC3") (pin "8") (pinfunction "COL_8") (pintype "passive"))
      (node (ref "R4") (pin "1") (pinfunction "1_1") (pintype "passive"))
    )
    (net (code "60") (name "Net-(IC2W-SK1)") (class "Default")
      (node (ref "IC2") (pin "4") (pinfunction "SK1_4") (pintype "passive"))
      (node (ref "IC4") (pin "8") (pinfunction "COL_8") (pintype "passive"))
      (node (ref "R18") (pin "1") (pinfunction "1_1") (pintype "passive"))
    )
    (net (code "61") (name "Net-(IC2X-SK1)") (class "Default")
      (node (ref "IC2") (pin "5") (pinfunction "SK1_5") (pintype "passive"))
      (node (ref "ST1") (pin "12") (pinfunction "12_12") (pintype "bidirectional"))
    )
    (net (code "62") (name "Net-(IC2Y-SK1)") (class "Default")
      (node (ref "IC2") (pin "6") (pinfunction "SK1_6") (pintype "passive"))
      (node (ref "IC6") (pin "8") (pinfunction "COL_8") (pintype "passive"))
      (node (ref "R21") (pin "1") (pinfunction "1_1") (pintype "passive"))
    )
    (net (code "63") (name "Net-(LCD-CONTR)") (class "Default")
      (node (ref "LCD") (pin "3") (pinfunction "CONTR_3") (pintype "input"))
      (node (ref "R2") (pin "2") (pinfunction "S_2") (pintype "passive"))
    )
    (net (code "64") (name "Net-(R12-Pad1)") (class "Default")
      (node (ref "R12") (pin "1") (pinfunction "1_1") (pintype "passive"))
      (node (ref "SV1") (pin "8") (pinfunction "8_8") (pintype "passive"))
    )
    (net (code "65") (name "Net-(R13-Pad1)") (class "Default")
      (node (ref "R13") (pin "1") (pinfunction "1_1") (pintype "passive"))
      (node (ref "SV1") (pin "6") (pinfunction "6_6") (pintype "passive"))
    )
    (net (code "66") (name "Net-(TP3-TP_13)") (class "Default")
      (node (ref "ST1") (pin "14") (pinfunction "14_14") (pintype "bidirectional"))
      (node (ref "TP3") (pin "TP") (pinfunction "TP_13_TP") (pintype "bidirectional"))
    )
    (net (code "67") (name "Net-(TP4-TP_13)") (class "Default")
      (node (ref "ST1") (pin "16") (pinfunction "16_16") (pintype "bidirectional"))
      (node (ref "TP4") (pin "TP") (pinfunction "TP_13_TP") (pintype "bidirectional"))
    )
    (net (code "68") (name "Net-(TP5-TP_13)") (class "Default")
      (node (ref "ST1") (pin "18") (pinfunction "18_18") (pintype "bidirectional"))
      (node (ref "TP5") (pin "TP") (pinfunction "TP_13_TP") (pintype "bidirectional"))
    )
    (net (code "69") (name "Net-(TP6-TP_13)") (class "Default")
      (node (ref "ST1") (pin "20") (pinfunction "20_20") (pintype "bidirectional"))
      (node (ref "TP6") (pin "TP") (pinfunction "TP_13_TP") (pintype "bidirectional"))
    )
    (net (code "70") (name "Net-(TP7-TP_13)") (class "Default")
      (node (ref "ST1") (pin "22") (pinfunction "22_22") (pintype "bidirectional"))
      (node (ref "TP7") (pin "TP") (pinfunction "TP_13_TP") (pintype "bidirectional"))
    )
    (net (code "71") (name "Net-(TP8-TP_13)") (class "Default")
      (node (ref "ST1") (pin "24") (pinfunction "24_24") (pintype "bidirectional"))
      (node (ref "TP8") (pin "TP") (pinfunction "TP_13_TP") (pintype "bidirectional"))
    )
    (net (code "72") (name "Net-(TP9-TP_13)") (class "Default")
      (node (ref "ST1") (pin "26") (pinfunction "26_26") (pintype "bidirectional"))
      (node (ref "TP9") (pin "TP") (pinfunction "TP_13_TP") (pintype "bidirectional"))
    )
    (net (code "73") (name "Net-(X1B-F)") (class "Default")
      (node (ref "R16") (pin "1") (pinfunction "1_1") (pintype "passive"))
      (node (ref "X1") (pin "10") (pinfunction "F_10") (pintype "passive"))
    )
    (net (code "74") (name "Net-(X1C-F)") (class "Default")
      (node (ref "R19") (pin "1") (pinfunction "1_1") (pintype "passive"))
      (node (ref "X1") (pin "11") (pinfunction "F_11") (pintype "passive"))
    )
    (net (code "75") (name "Net-(X1D-F)") (class "Default")
      (node (ref "R22") (pin "1") (pinfunction "1_1") (pintype "passive"))
      (node (ref "X1") (pin "12") (pinfunction "F_12") (pintype "passive"))
    )
    (net (code "76") (name "Net-(X1G-F)") (class "Default")
      (node (ref "R10") (pin "1") (pinfunction "1_1") (pintype "passive"))
      (node (ref "X1") (pin "15") (pinfunction "F_15") (pintype "passive"))
    )
    (net (code "77") (name "Net-(X1M-F)") (class "Default")
      (node (ref "C31") (pin "2") (pinfunction "2_2") (pintype "passive"))
      (node (ref "L3") (pin "1") (pinfunction "1_1") (pintype "passive"))
      (node (ref "X1") (pin "7") (pinfunction "F_7") (pintype "passive"))
    )
    (net (code "78") (name "Net-(X1O-F)") (class "Default")
      (node (ref "R14") (pin "1") (pinfunction "1_1") (pintype "passive"))
      (node (ref "X1") (pin "9") (pinfunction "F_9") (pintype "passive"))
    )
    (net (code "79") (name "V+") (class "Default")
      (node (ref "DC1") (pin "24") (pinfunction "+VIN1_24") (pintype "passive"))
      (node (ref "DC2") (pin "24") (pinfunction "+VIN1_24") (pintype "passive"))
    )
    (net (code "80") (name "unconnected-(C7-Pad+)") (class "Default")
      (node (ref "C7") (pin "+") (pinfunction "+_+") (pintype "passive"))
    )
    (net (code "81") (name "unconnected-(C7-Pad-)") (class "Default")
      (node (ref "C7") (pin "-") (pinfunction "-_-") (pintype "passive"))
    )
    (net (code "82") (name "unconnected-(C8-Pad+)") (class "Default")
      (node (ref "C8") (pin "+") (pinfunction "+_+") (pintype "passive"))
    )
    (net (code "83") (name "unconnected-(C8-Pad-)") (class "Default")
      (node (ref "C8") (pin "-") (pinfunction "-_-") (pintype "passive"))
    )
    (net (code "84") (name "unconnected-(C9-Pad+)") (class "Default")
      (node (ref "C9") (pin "+") (pinfunction "+_+") (pintype "passive"))
    )
    (net (code "85") (name "unconnected-(C9-Pad-)") (class "Default")
      (node (ref "C9") (pin "-") (pinfunction "-_-") (pintype "passive"))
    )
    (net (code "86") (name "unconnected-(C10-Pad1)") (class "Default")
      (node (ref "C10") (pin "1") (pinfunction "1_1") (pintype "passive"))
    )
    (net (code "87") (name "unconnected-(C10-Pad2)") (class "Default")
      (node (ref "C10") (pin "2") (pinfunction "2_2") (pintype "passive"))
    )
    (net (code "88") (name "unconnected-(C23-Pad+)") (class "Default")
      (node (ref "C23") (pin "+") (pinfunction "+_+") (pintype "passive"))
    )
    (net (code "89") (name "unconnected-(C23-Pad-)") (class "Default")
      (node (ref "C23") (pin "-") (pinfunction "-_-") (pintype "passive"))
    )
    (net (code "90") (name "unconnected-(C26-Pad1)") (class "Default")
      (node (ref "C26") (pin "1") (pinfunction "1_1") (pintype "passive"))
    )
    (net (code "91") (name "unconnected-(C26-Pad2)") (class "Default")
      (node (ref "C26") (pin "2") (pinfunction "2_2") (pintype "passive"))
    )
    (net (code "92") (name "unconnected-(C27-Pad1)") (class "Default")
      (node (ref "C27") (pin "1") (pinfunction "1_1") (pintype "passive"))
    )
    (net (code "93") (name "unconnected-(C27-Pad2)") (class "Default")
      (node (ref "C27") (pin "2") (pinfunction "2_2") (pintype "passive"))
    )
    (net (code "94") (name "unconnected-(DC1-+VIN-Pad1)") (class "Default")
      (node (ref "DC1") (pin "1") (pinfunction "+VIN_1") (pintype "passive"))
    )
    (net (code "95") (name "unconnected-(DC1-+VOUT-Pad11)") (class "Default")
      (node (ref "DC1") (pin "11") (pinfunction "+VOUT_11") (pintype "passive"))
    )
    (net (code "96") (name "unconnected-(DC1--VIN-Pad12)") (class "Default")
      (node (ref "DC1") (pin "12") (pinfunction "-VIN_12") (pintype "passive"))
    )
    (net (code "97") (name "unconnected-(DC1--VOUT-Pad10)") (class "Default")
      (node (ref "DC1") (pin "10") (pinfunction "-VOUT_10") (pintype "passive"))
    )
    (net (code "98") (name "unconnected-(DC2-+VIN-Pad1)") (class "Default")
      (node (ref "DC2") (pin "1") (pinfunction "+VIN_1") (pintype "passive"))
    )
    (net (code "99") (name "unconnected-(DC2-+VOUT-Pad11)") (class "Default")
      (node (ref "DC2") (pin "11") (pinfunction "+VOUT_11") (pintype "passive"))
    )
    (net (code "100") (name "unconnected-(DC2--VIN-Pad12)") (class "Default")
      (node (ref "DC2") (pin "12") (pinfunction "-VIN_12") (pintype "passive"))
    )
    (net (code "101") (name "unconnected-(DC2--VOUT-Pad10)") (class "Default")
      (node (ref "DC2") (pin "10") (pinfunction "-VOUT_10") (pintype "passive"))
    )
    (net (code "102") (name "unconnected-(DISP1-D0-Pad7)") (class "Default")
      (node (ref "DISP1") (pin "7") (pinfunction "D0_7") (pintype "bidirectional"))
    )
    (net (code "103") (name "unconnected-(DISP1-D1-Pad8)") (class "Default")
      (node (ref "DISP1") (pin "8") (pinfunction "D1_8") (pintype "bidirectional"))
    )
    (net (code "104") (name "unconnected-(DISP1-D2-Pad9)") (class "Default")
      (node (ref "DISP1") (pin "9") (pinfunction "D2_9") (pintype "bidirectional"))
    )
    (net (code "105") (name "unconnected-(DISP1-D3-Pad10)") (class "Default")
      (node (ref "DISP1") (pin "10") (pinfunction "D3_10") (pintype "bidirectional"))
    )
    (net (code "106") (name "unconnected-(DISP1-LED+-Pad15)") (class "Default")
      (node (ref "DISP1") (pin "15") (pinfunction "LED+_15") (pintype "input"))
    )
    (net (code "107") (name "unconnected-(DISP1-LED--Pad16)") (class "Default")
      (node (ref "DISP1") (pin "16") (pinfunction "LED-_16") (pintype "input"))
    )
    (net (code "108") (name "unconnected-(JP1-Pad2)") (class "Default")
      (node (ref "JP1") (pin "2") (pinfunction "2_2") (pintype "passive"))
    )
    (net (code "109") (name "unconnected-(JP1-Pad6)") (class "Default")
      (node (ref "JP1") (pin "6") (pinfunction "6_6") (pintype "passive"))
    )
    (net (code "110") (name "unconnected-(L1-Pad1)") (class "Default")
      (node (ref "L1") (pin "1") (pinfunction "1_1") (pintype "passive"))
    )
    (net (code "111") (name "unconnected-(L1-Pad2)") (class "Default")
      (node (ref "L1") (pin "2") (pinfunction "2_2") (pintype "passive"))
    )
    (net (code "112") (name "unconnected-(L4-Pad1)") (class "Default")
      (node (ref "L4") (pin "1") (pinfunction "1_1") (pintype "passive"))
    )
    (net (code "113") (name "unconnected-(L4-Pad2)") (class "Default")
      (node (ref "L4") (pin "2") (pinfunction "2_2") (pintype "passive"))
    )
    (net (code "114") (name "unconnected-(LCD-D0-Pad7)") (class "Default")
      (node (ref "LCD") (pin "7") (pinfunction "D0_7") (pintype "input"))
    )
    (net (code "115") (name "unconnected-(LCD-D1-Pad8)") (class "Default")
      (node (ref "LCD") (pin "8") (pinfunction "D1_8") (pintype "input"))
    )
    (net (code "116") (name "unconnected-(LCD-D2-Pad9)") (class "Default")
      (node (ref "LCD") (pin "9") (pinfunction "D2_9") (pintype "input"))
    )
    (net (code "117") (name "unconnected-(LCD-D3-Pad10)") (class "Default")
      (node (ref "LCD") (pin "10") (pinfunction "D3_10") (pintype "input"))
    )
    (net (code "118") (name "unconnected-(LCD-NC-Pad15)") (class "Default")
      (node (ref "LCD") (pin "15") (pinfunction "NC_15") (pintype "no_connect"))
    )
    (net (code "119") (name "unconnected-(LCD-NC-Pad16)") (class "Default")
      (node (ref "LCD") (pin "16") (pinfunction "NC_16") (pintype "no_connect"))
    )
    (net (code "120") (name "unconnected-(R8-Pad1)") (class "Default")
      (node (ref "R8") (pin "1") (pinfunction "1_1") (pintype "passive"))
    )
    (net (code "121") (name "unconnected-(R8-Pad2)") (class "Default")
      (node (ref "R8") (pin "2") (pinfunction "2_2") (pintype "passive"))
    )
    (net (code "122") (name "unconnected-(R9-Pad1)") (class "Default")
      (node (ref "R9") (pin "1") (pinfunction "1_1") (pintype "passive"))
    )
    (net (code "123") (name "unconnected-(R9-Pad2)") (class "Default")
      (node (ref "R9") (pin "2") (pinfunction "2_2") (pintype "passive"))
    )
    (net (code "124") (name "unconnected-(UB-S-Pad2)") (class "Default")
      (node (ref "U") (pin "2") (pinfunction "S_2") (pintype "passive"))
    )
    (net (code "125") (name "unconnected-(X1-PadG1)") (class "Default")
      (node (ref "X1") (pin "G1") (pinfunction "G1_G1") (pintype "passive"))
    )
    (net (code "126") (name "unconnected-(X1-PadG2)") (class "Default")
      (node (ref "X1") (pin "G2") (pinfunction "G2_G2") (pintype "passive"))
    )
    (net (code "127") (name "unconnected-(X1E-F-Pad13)") (class "Default")
      (node (ref "X1") (pin "13") (pinfunction "F_13") (pintype "passive"))
    )
    (net (code "128") (name "unconnected-(X1F-F-Pad14)") (class "Default")
      (node (ref "X1") (pin "14") (pinfunction "F_14") (pintype "passive"))
    )
    (net (code "129") (name "unconnected-(X1K-F-Pad5)") (class "Default")
      (node (ref "X1") (pin "5") (pinfunction "F_5") (pintype "passive"))
    )
    (net (code "130") (name "unconnected-(X1L-F-Pad6)") (class "Default")
      (node (ref "X1") (pin "6") (pinfunction "F_6") (pintype "passive"))
    )
  )
)
